# v1garagedoor.net
KiCad netlist of a schematic drawn in EAGLE
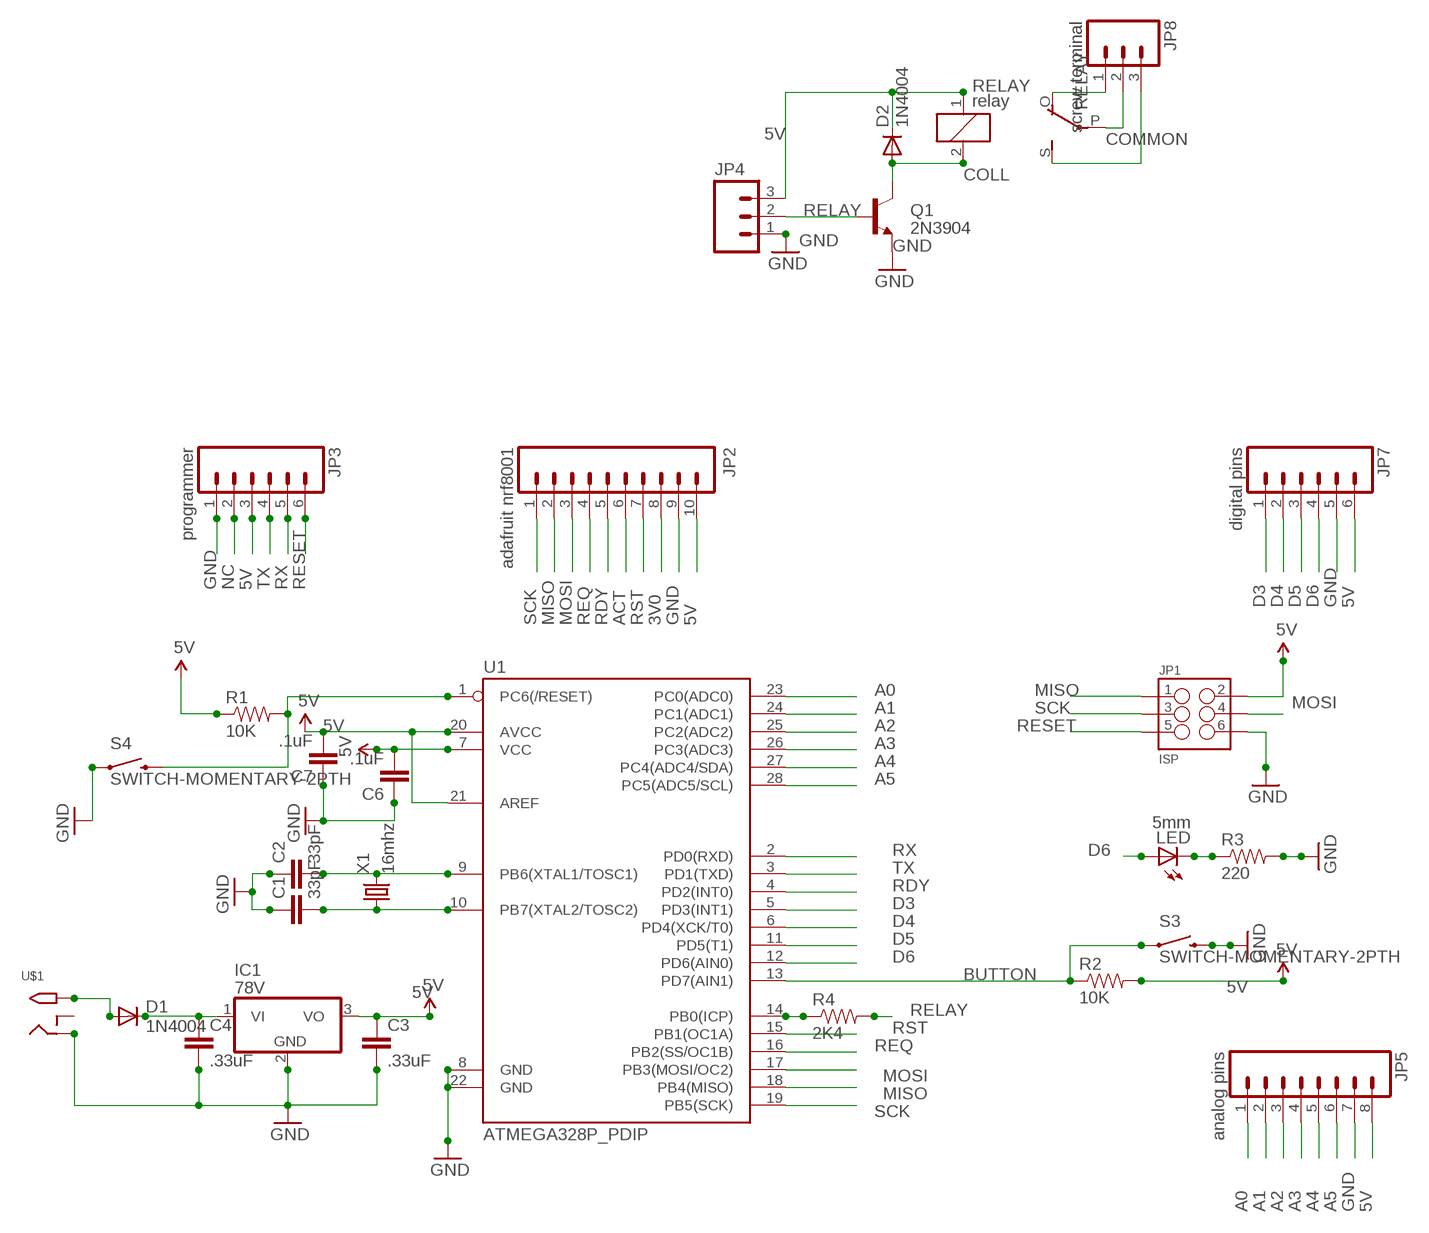
[diagram p0: schematic, sheet 1]

(export (version "E")
  (design (tool "Eeschema 10.0.6"))
  (components
    (comp (ref "C1")
      (value "33pF")
      (footprint "eagle-import:CAP-PTH-5MM")
      (libsource (lib "eagle-import") (part "CAPPTH1"))
    )
    (comp (ref "C2")
      (value "33pF")
      (footprint "eagle-import:CAP-PTH-5MM")
      (libsource (lib "eagle-import") (part "CAPPTH1"))
    )
    (comp (ref "C3")
      (value ".33uF")
      (footprint "eagle-import:CAP-PTH-SMALL-KIT")
      (libsource (lib "eagle-import") (part "CAPKIT"))
    )
    (comp (ref "C4")
      (value ".33uF")
      (footprint "eagle-import:CAP-PTH-SMALL-KIT")
      (libsource (lib "eagle-import") (part "CAPKIT"))
    )
    (comp (ref "C6")
      (value ".1uF")
      (footprint "eagle-import:CAP-PTH-SMALL-KIT")
      (libsource (lib "eagle-import") (part "CAPKIT"))
    )
    (comp (ref "C7")
      (value ".1uF")
      (footprint "eagle-import:CAP-PTH-SMALL-KIT")
      (libsource (lib "eagle-import") (part "CAPKIT"))
    )
    (comp (ref "D1")
      (value "1N4004")
      (footprint "eagle-import:DO41-10")
      (libsource (lib "eagle-import") (part "1N4004"))
    )
    (comp (ref "D2")
      (value "1N4004")
      (footprint "eagle-import:DO41-10")
      (libsource (lib "eagle-import") (part "1N4004"))
    )
    (comp (ref "IC1")
      (value "78V")
      (footprint "eagle-import:TO220V")
      (libsource (lib "eagle-import") (part "78V"))
    )
    (comp (ref "JP1")
      (value "ISP")
      (footprint "eagle-import:2X3-NS")
      (libsource (lib "eagle-import") (part "M03X2NO_SILK"))
    )
    (comp (ref "JP2")
      (value "adafruit nrf8001")
      (footprint "eagle-import:1X10")
      (libsource (lib "eagle-import") (part "M10SILK_FEMALE_PTH"))
    )
    (comp (ref "JP3")
      (value "programmer")
      (footprint "eagle-import:1X06_NO_SILK")
      (libsource (lib "eagle-import") (part "M06NO_SILK_FEMALE_PTH"))
    )
    (comp (ref "JP4")
      (value "M03LOCK")
      (footprint "eagle-import:1X03_LOCK")
      (libsource (lib "eagle-import") (part "M03LOCK"))
    )
    (comp (ref "JP5")
      (value "analog pins")
      (footprint "eagle-import:1X08")
      (libsource (lib "eagle-import") (part "M08SILK_FEMALE_PTH"))
    )
    (comp (ref "JP7")
      (value "digital pins")
      (footprint "eagle-import:1X06_NO_SILK")
      (libsource (lib "eagle-import") (part "M06NO_SILK_FEMALE_PTH"))
    )
    (comp (ref "JP8")
      (value "screw terminal")
      (footprint "eagle-import:SCREWTERMINAL-3.5MM-3")
      (libsource (lib "eagle-import") (part "M03SCREW"))
    )
    (comp (ref "LED")
      (value "5mm")
      (footprint "eagle-import:LED5MM")
      (libsource (lib "eagle-import") (part "LED5MM"))
    )
    (comp (ref "Q1")
      (value "2N3904")
      (footprint "eagle-import:TO-92")
      (libsource (lib "eagle-import") (part "TRANSISTOR_NPN2N3904"))
    )
    (comp (ref "R1")
      (value "10K")
      (footprint "eagle-import:AXIAL-0.3")
      (libsource (lib "eagle-import") (part "RESISTORAXIAL-0.3"))
    )
    (comp (ref "R2")
      (value "10K")
      (footprint "eagle-import:AXIAL-0.3")
      (libsource (lib "eagle-import") (part "RESISTORAXIAL-0.3"))
    )
    (comp (ref "R3")
      (value "220")
      (footprint "eagle-import:AXIAL-0.3")
      (libsource (lib "eagle-import") (part "RESISTORAXIAL-0.3"))
    )
    (comp (ref "R4")
      (value "2K4")
      (footprint "eagle-import:AXIAL-0.3")
      (libsource (lib "eagle-import") (part "RESISTORAXIAL-0.3"))
    )
    (comp (ref "RELAY")
      (value "relay")
      (footprint "eagle-import:ZF112")
      (fields (field (name "MOUSER") "655-ORWH-SH105D1F000"))
      (libsource (lib "eagle-import") (part "ZF112"))
    )
    (comp (ref "S3")
      (value "SWITCH-MOMENTARY-2PTH")
      (footprint "eagle-import:TACTILE-PTH")
      (libsource (lib "eagle-import") (part "SWITCH-MOMENTARY-2PTH"))
    )
    (comp (ref "S4")
      (value "SWITCH-MOMENTARY-2PTH")
      (footprint "eagle-import:TACTILE-PTH")
      (libsource (lib "eagle-import") (part "SWITCH-MOMENTARY-2PTH"))
    )
    (comp (ref "U$1")
      (value "2.1MMJACKTHM")
      (footprint "eagle-import:PJ-102A")
      (libsource (lib "eagle-import") (part "2.1MMJACKTHM"))
    )
    (comp (ref "U1")
      (value "ATMEGA328P_PDIP")
      (footprint "eagle-import:DIL28-3")
      (libsource (lib "eagle-import") (part "ATMEGA328P_PDIP"))
    )
    (comp (ref "X1")
      (value "16mhz")
      (footprint "eagle-import:TC38H")
      (libsource (lib "eagle-import") (part "CRYSTALTC38H"))
    )
  )
  (nets
    (net (code "1") (name "/3V0") (class "Default")
      (node (ref "JP2") (pin "8") (pinfunction "8_8") (pintype "passive"))
    )
    (net (code "2") (name "/A0") (class "Default")
      (node (ref "JP5") (pin "1") (pinfunction "1_1") (pintype "passive"))
      (node (ref "U1") (pin "23") (pinfunction "PC0(ADC0)_23") (pintype "bidirectional"))
    )
    (net (code "3") (name "/A1") (class "Default")
      (node (ref "JP5") (pin "2") (pinfunction "2_2") (pintype "passive"))
      (node (ref "U1") (pin "24") (pinfunction "PC1(ADC1)_24") (pintype "bidirectional"))
    )
    (net (code "4") (name "/A2") (class "Default")
      (node (ref "JP5") (pin "3") (pinfunction "3_3") (pintype "passive"))
      (node (ref "U1") (pin "25") (pinfunction "PC2(ADC2)_25") (pintype "bidirectional"))
    )
    (net (code "5") (name "/A3") (class "Default")
      (node (ref "JP5") (pin "4") (pinfunction "4_4") (pintype "passive"))
      (node (ref "U1") (pin "26") (pinfunction "PC3(ADC3)_26") (pintype "bidirectional"))
    )
    (net (code "6") (name "/A4") (class "Default")
      (node (ref "JP5") (pin "5") (pinfunction "5_5") (pintype "passive"))
      (node (ref "U1") (pin "27") (pinfunction "PC4(ADC4/SDA)_27") (pintype "bidirectional"))
    )
    (net (code "7") (name "/A5") (class "Default")
      (node (ref "JP5") (pin "6") (pinfunction "6_6") (pintype "passive"))
      (node (ref "U1") (pin "28") (pinfunction "PC5(ADC5/SCL)_28") (pintype "bidirectional"))
    )
    (net (code "8") (name "/ACT") (class "Default")
      (node (ref "JP2") (pin "6") (pinfunction "6_6") (pintype "passive"))
    )
    (net (code "9") (name "/BUTTON") (class "Default")
      (node (ref "R2") (pin "P$1") (pinfunction "1_P$1") (pintype "passive"))
      (node (ref "S3") (pin "1") (pinfunction "1_1") (pintype "passive"))
      (node (ref "U1") (pin "13") (pinfunction "PD7(AIN1)_13") (pintype "bidirectional"))
    )
    (net (code "10") (name "/COLL") (class "Default")
      (node (ref "D2") (pin "A") (pinfunction "A_A") (pintype "passive"))
      (node (ref "Q1") (pin "3") (pinfunction "C_3") (pintype "passive"))
      (node (ref "RELAY") (pin "2") (pinfunction "2_2") (pintype "passive"))
    )
    (net (code "11") (name "/COMMON") (class "Default")
      (node (ref "JP8") (pin "2") (pinfunction "2_2") (pintype "passive"))
      (node (ref "RELAY") (pin "P") (pinfunction "P_P") (pintype "passive"))
    )
    (net (code "12") (name "/D3") (class "Default")
      (node (ref "JP7") (pin "1") (pinfunction "1_1") (pintype "passive"))
      (node (ref "U1") (pin "5") (pinfunction "PD3(INT1)_5") (pintype "bidirectional"))
    )
    (net (code "13") (name "/D4") (class "Default")
      (node (ref "JP7") (pin "2") (pinfunction "2_2") (pintype "passive"))
      (node (ref "U1") (pin "6") (pinfunction "PD4(XCK/T0)_6") (pintype "bidirectional"))
    )
    (net (code "14") (name "/D5") (class "Default")
      (node (ref "JP7") (pin "3") (pinfunction "3_3") (pintype "passive"))
      (node (ref "U1") (pin "11") (pinfunction "PD5(T1)_11") (pintype "bidirectional"))
    )
    (net (code "15") (name "/D6") (class "Default")
      (node (ref "JP7") (pin "4") (pinfunction "4_4") (pintype "passive"))
      (node (ref "LED") (pin "A") (pinfunction "A_A") (pintype "passive"))
      (node (ref "U1") (pin "12") (pinfunction "PD6(AIN0)_12") (pintype "bidirectional"))
    )
    (net (code "16") (name "/MISO") (class "Default")
      (node (ref "JP1") (pin "1") (pinfunction "1_1") (pintype "bidirectional"))
      (node (ref "JP2") (pin "2") (pinfunction "2_2") (pintype "passive"))
      (node (ref "U1") (pin "18") (pinfunction "PB4(MISO)_18") (pintype "bidirectional"))
    )
    (net (code "17") (name "/MOSI") (class "Default")
      (node (ref "JP1") (pin "4") (pinfunction "4_4") (pintype "bidirectional"))
      (node (ref "JP2") (pin "3") (pinfunction "3_3") (pintype "passive"))
      (node (ref "U1") (pin "17") (pinfunction "PB3(MOSI/OC2)_17") (pintype "bidirectional"))
    )
    (net (code "18") (name "/NC") (class "Default")
      (node (ref "JP3") (pin "2") (pinfunction "2_2") (pintype "passive"))
    )
    (net (code "19") (name "/RDY") (class "Default")
      (node (ref "JP2") (pin "5") (pinfunction "5_5") (pintype "passive"))
      (node (ref "U1") (pin "4") (pinfunction "PD2(INT0)_4") (pintype "bidirectional"))
    )
    (net (code "20") (name "/RELAY") (class "Default")
      (node (ref "JP4") (pin "2") (pinfunction "2_2") (pintype "passive"))
      (node (ref "Q1") (pin "2") (pinfunction "B_2") (pintype "passive"))
      (node (ref "R4") (pin "P$2") (pinfunction "2_P$2") (pintype "passive"))
    )
    (net (code "21") (name "/REQ") (class "Default")
      (node (ref "JP2") (pin "4") (pinfunction "4_4") (pintype "passive"))
      (node (ref "U1") (pin "16") (pinfunction "PB2(SS/OC1B)_16") (pintype "bidirectional"))
    )
    (net (code "22") (name "/RESET") (class "Default")
      (node (ref "JP1") (pin "5") (pinfunction "5_5") (pintype "bidirectional"))
      (node (ref "JP3") (pin "6") (pinfunction "6_6") (pintype "passive"))
      (node (ref "R1") (pin "P$2") (pinfunction "2_P$2") (pintype "passive"))
      (node (ref "S4") (pin "3") (pinfunction "2_3") (pintype "passive"))
      (node (ref "U1") (pin "1") (pinfunction "PC6(/RESET)_1") (pintype "bidirectional"))
    )
    (net (code "23") (name "/RST") (class "Default")
      (node (ref "JP2") (pin "7") (pinfunction "7_7") (pintype "passive"))
      (node (ref "U1") (pin "15") (pinfunction "PB1(OC1A)_15") (pintype "bidirectional"))
    )
    (net (code "24") (name "/RX") (class "Default")
      (node (ref "JP3") (pin "5") (pinfunction "5_5") (pintype "passive"))
      (node (ref "U1") (pin "2") (pinfunction "PD0(RXD)_2") (pintype "bidirectional"))
    )
    (net (code "25") (name "/SCK") (class "Default")
      (node (ref "JP1") (pin "3") (pinfunction "3_3") (pintype "bidirectional"))
      (node (ref "JP2") (pin "1") (pinfunction "1_1") (pintype "passive"))
      (node (ref "U1") (pin "19") (pinfunction "PB5(SCK)_19") (pintype "bidirectional"))
    )
    (net (code "26") (name "/TX") (class "Default")
      (node (ref "JP3") (pin "4") (pinfunction "4_4") (pintype "passive"))
      (node (ref "U1") (pin "3") (pinfunction "PD1(TXD)_3") (pintype "bidirectional"))
    )
    (net (code "27") (name "5V") (class "Default")
      (node (ref "C3") (pin "1") (pinfunction "1_1") (pintype "passive"))
      (node (ref "C6") (pin "2") (pinfunction "2_2") (pintype "passive"))
      (node (ref "C7") (pin "2") (pinfunction "2_2") (pintype "passive"))
      (node (ref "D2") (pin "C") (pinfunction "C_C") (pintype "passive"))
      (node (ref "IC1") (pin "3") (pinfunction "VO_3") (pintype "passive"))
      (node (ref "JP1") (pin "2") (pinfunction "2_2") (pintype "bidirectional"))
      (node (ref "JP2") (pin "10") (pinfunction "10_10") (pintype "passive"))
      (node (ref "JP3") (pin "3") (pinfunction "3_3") (pintype "passive"))
      (node (ref "JP4") (pin "3") (pinfunction "3_3") (pintype "passive"))
      (node (ref "JP5") (pin "8") (pinfunction "8_8") (pintype "passive"))
      (node (ref "JP7") (pin "6") (pinfunction "6_6") (pintype "passive"))
      (node (ref "R1") (pin "P$1") (pinfunction "1_P$1") (pintype "passive"))
      (node (ref "R2") (pin "P$2") (pinfunction "2_P$2") (pintype "passive"))
      (node (ref "RELAY") (pin "1") (pinfunction "1_1") (pintype "passive"))
      (node (ref "U1") (pin "20") (pinfunction "AVCC_20") (pintype "bidirectional"))
      (node (ref "U1") (pin "21") (pinfunction "AREF_21") (pintype "bidirectional"))
      (node (ref "U1") (pin "7") (pinfunction "VCC_7") (pintype "bidirectional"))
    )
    (net (code "28") (name "GND") (class "Default")
      (node (ref "C1") (pin "1") (pinfunction "1_1") (pintype "passive"))
      (node (ref "C2") (pin "1") (pinfunction "1_1") (pintype "passive"))
      (node (ref "C3") (pin "2") (pinfunction "2_2") (pintype "passive"))
      (node (ref "C4") (pin "2") (pinfunction "2_2") (pintype "passive"))
      (node (ref "C6") (pin "1") (pinfunction "1_1") (pintype "passive"))
      (node (ref "C7") (pin "1") (pinfunction "1_1") (pintype "passive"))
      (node (ref "IC1") (pin "2") (pinfunction "GND_2") (pintype "passive"))
      (node (ref "JP1") (pin "6") (pinfunction "6_6") (pintype "bidirectional"))
      (node (ref "JP2") (pin "9") (pinfunction "9_9") (pintype "passive"))
      (node (ref "JP3") (pin "1") (pinfunction "1_1") (pintype "passive"))
      (node (ref "JP4") (pin "1") (pinfunction "1_1") (pintype "passive"))
      (node (ref "JP5") (pin "7") (pinfunction "7_7") (pintype "passive"))
      (node (ref "JP7") (pin "5") (pinfunction "5_5") (pintype "passive"))
      (node (ref "Q1") (pin "1") (pinfunction "E_1") (pintype "passive"))
      (node (ref "R3") (pin "P$2") (pinfunction "2_P$2") (pintype "passive"))
      (node (ref "S3") (pin "3") (pinfunction "2_3") (pintype "passive"))
      (node (ref "S4") (pin "1") (pinfunction "1_1") (pintype "passive"))
      (node (ref "U$1") (pin "RING") (pinfunction "RING_RING") (pintype "bidirectional"))
      (node (ref "U1") (pin "22") (pinfunction "GND_22") (pintype "bidirectional"))
      (node (ref "U1") (pin "8") (pinfunction "GND_8") (pintype "bidirectional"))
    )
    (net (code "29") (name "Net-(D1-PadA)") (class "Default")
      (node (ref "D1") (pin "A") (pinfunction "A_A") (pintype "passive"))
      (node (ref "U$1") (pin "TIP") (pinfunction "TIP_TIP") (pintype "bidirectional"))
    )
    (net (code "30") (name "Net-(IC1-VI)") (class "Default")
      (node (ref "C4") (pin "1") (pinfunction "1_1") (pintype "passive"))
      (node (ref "D1") (pin "C") (pinfunction "C_C") (pintype "passive"))
      (node (ref "IC1") (pin "1") (pinfunction "VI_1") (pintype "input"))
    )
    (net (code "31") (name "Net-(JP8-Pad1)") (class "Default")
      (node (ref "JP8") (pin "1") (pinfunction "1_1") (pintype "passive"))
      (node (ref "RELAY") (pin "O") (pinfunction "O_O") (pintype "passive"))
    )
    (net (code "32") (name "Net-(JP8-Pad3)") (class "Default")
      (node (ref "JP8") (pin "3") (pinfunction "3_3") (pintype "passive"))
      (node (ref "RELAY") (pin "S") (pinfunction "S_S") (pintype "passive"))
    )
    (net (code "33") (name "Net-(LED-C)") (class "Default")
      (node (ref "LED") (pin "K") (pinfunction "C_K") (pintype "passive"))
      (node (ref "R3") (pin "P$1") (pinfunction "1_P$1") (pintype "passive"))
    )
    (net (code "34") (name "Net-(R4-1)") (class "Default")
      (node (ref "R4") (pin "P$1") (pinfunction "1_P$1") (pintype "passive"))
      (node (ref "U1") (pin "14") (pinfunction "PB0(ICP)_14") (pintype "bidirectional"))
    )
    (net (code "35") (name "Net-(U1-PB6(XTAL1{slash}TOSC1))") (class "Default")
      (node (ref "C2") (pin "2") (pinfunction "2_2") (pintype "passive"))
      (node (ref "U1") (pin "9") (pinfunction "PB6(XTAL1/TOSC1)_9") (pintype "bidirectional"))
      (node (ref "X1") (pin "2") (pinfunction "2_2") (pintype "passive"))
    )
    (net (code "36") (name "Net-(U1-PB7(XTAL2{slash}TOSC2))") (class "Default")
      (node (ref "C1") (pin "2") (pinfunction "2_2") (pintype "passive"))
      (node (ref "U1") (pin "10") (pinfunction "PB7(XTAL2/TOSC2)_10") (pintype "bidirectional"))
      (node (ref "X1") (pin "1") (pinfunction "1_1") (pintype "passive"))
    )
    (net (code "37") (name "unconnected-(U$1-PadRING_SW)") (class "Default")
      (node (ref "U$1") (pin "RING_SW") (pinfunction "RING_SW_RING_SW") (pintype "bidirectional"))
    )
  )
)
